# W033C.net
KiCad netlist of a schematic drawn in EAGLE
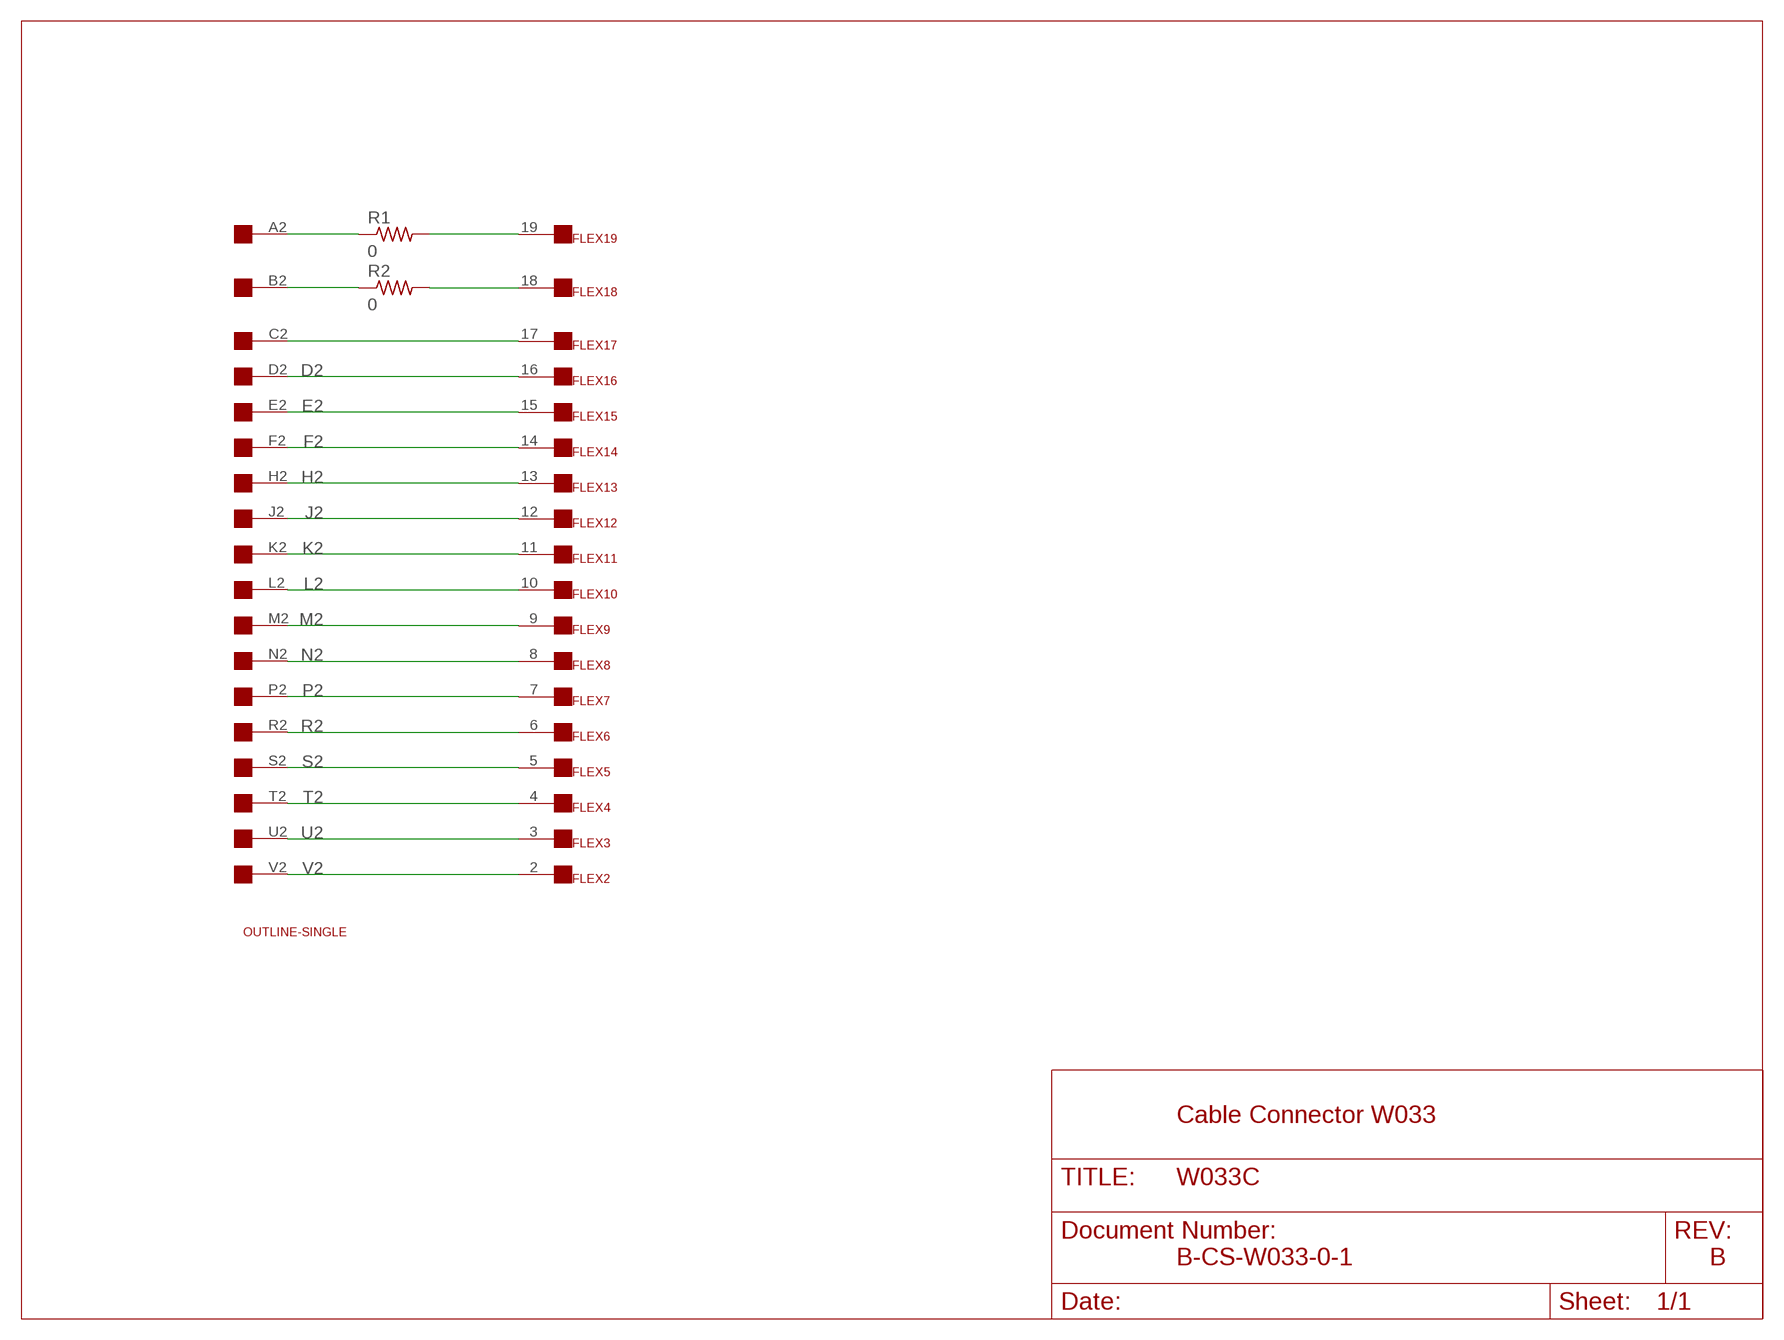
[diagram p0: schematic, sheet 1]

(export (version "E")
  (design (tool "Eeschema 10.0.6"))
  (components
    (comp (ref "FLEX")
      (value "FLEX19")
      (footprint "eagle-import:FLEX19")
      (libsource (lib "eagle-import") (part "FLEX19"))
    )
    (comp (ref "R1")
      (value "0")
      (footprint "eagle-import:0207_10")
      (libsource (lib "eagle-import") (part "R-US_0207/10"))
    )
    (comp (ref "R2")
      (value "0")
      (footprint "eagle-import:0207_10")
      (libsource (lib "eagle-import") (part "R-US_0207/10"))
    )
    (comp (ref "U$1")
      (value "OUTLINE-SINGLE")
      (footprint "eagle-import:SINGLE")
      (libsource (lib "eagle-import") (part "OUTLINE-SINGLE"))
    )
    (comp (ref "U$2")
      (value "EDGE-1")
      (footprint "eagle-import:EDGE-CON1")
      (libsource (lib "eagle-import") (part "EDGE-1"))
    )
  )
  (nets
    (net (code "1") (name "/D2") (class "Default")
      (node (ref "FLEX") (pin "16") (pinfunction "1_16") (pintype "passive"))
      (node (ref "U$2") (pin "D2") (pinfunction "1_D2") (pintype "bidirectional"))
    )
    (net (code "2") (name "/E2") (class "Default")
      (node (ref "FLEX") (pin "15") (pinfunction "1_15") (pintype "passive"))
      (node (ref "U$2") (pin "E2") (pinfunction "1_E2") (pintype "bidirectional"))
    )
    (net (code "3") (name "/F2") (class "Default")
      (node (ref "FLEX") (pin "14") (pinfunction "1_14") (pintype "passive"))
      (node (ref "U$2") (pin "F2") (pinfunction "1_F2") (pintype "bidirectional"))
    )
    (net (code "4") (name "/H2") (class "Default")
      (node (ref "FLEX") (pin "13") (pinfunction "1_13") (pintype "passive"))
      (node (ref "U$2") (pin "H2") (pinfunction "1_H2") (pintype "bidirectional"))
    )
    (net (code "5") (name "/J2") (class "Default")
      (node (ref "FLEX") (pin "12") (pinfunction "1_12") (pintype "passive"))
      (node (ref "U$2") (pin "J2") (pinfunction "1_J2") (pintype "bidirectional"))
    )
    (net (code "6") (name "/K2") (class "Default")
      (node (ref "FLEX") (pin "11") (pinfunction "1_11") (pintype "passive"))
      (node (ref "U$2") (pin "K2") (pinfunction "1_K2") (pintype "bidirectional"))
    )
    (net (code "7") (name "/L2") (class "Default")
      (node (ref "FLEX") (pin "10") (pinfunction "1_10") (pintype "passive"))
      (node (ref "U$2") (pin "L2") (pinfunction "1_L2") (pintype "bidirectional"))
    )
    (net (code "8") (name "/M2") (class "Default")
      (node (ref "FLEX") (pin "9") (pinfunction "1_9") (pintype "passive"))
      (node (ref "U$2") (pin "M2") (pinfunction "1_M2") (pintype "bidirectional"))
    )
    (net (code "9") (name "/N2") (class "Default")
      (node (ref "FLEX") (pin "8") (pinfunction "1_8") (pintype "passive"))
      (node (ref "U$2") (pin "N2") (pinfunction "1_N2") (pintype "bidirectional"))
    )
    (net (code "10") (name "/P2") (class "Default")
      (node (ref "FLEX") (pin "7") (pinfunction "1_7") (pintype "passive"))
      (node (ref "U$2") (pin "P2") (pinfunction "1_P2") (pintype "bidirectional"))
    )
    (net (code "11") (name "/R2") (class "Default")
      (node (ref "FLEX") (pin "6") (pinfunction "1_6") (pintype "passive"))
      (node (ref "U$2") (pin "R2") (pinfunction "1_R2") (pintype "bidirectional"))
    )
    (net (code "12") (name "/S2") (class "Default")
      (node (ref "FLEX") (pin "5") (pinfunction "1_5") (pintype "passive"))
      (node (ref "U$2") (pin "S2") (pinfunction "1_S2") (pintype "bidirectional"))
    )
    (net (code "13") (name "/T2") (class "Default")
      (node (ref "FLEX") (pin "4") (pinfunction "1_4") (pintype "passive"))
      (node (ref "U$2") (pin "T2") (pinfunction "1_T2") (pintype "bidirectional"))
    )
    (net (code "14") (name "/U2") (class "Default")
      (node (ref "FLEX") (pin "3") (pinfunction "1_3") (pintype "passive"))
      (node (ref "U$2") (pin "U2") (pinfunction "1_U2") (pintype "bidirectional"))
    )
    (net (code "15") (name "/V2") (class "Default")
      (node (ref "FLEX") (pin "2") (pinfunction "1_2") (pintype "passive"))
      (node (ref "U$2") (pin "V2") (pinfunction "1_V2") (pintype "bidirectional"))
    )
    (net (code "16") (name "Net-(FLEXI-1)") (class "Default")
      (node (ref "FLEX") (pin "17") (pinfunction "1_17") (pintype "passive"))
      (node (ref "U$2") (pin "C2") (pinfunction "1_C2") (pintype "bidirectional"))
    )
    (net (code "17") (name "Net-(FLEXJ-1)") (class "Default")
      (node (ref "FLEX") (pin "18") (pinfunction "1_18") (pintype "passive"))
      (node (ref "R2") (pin "2") (pinfunction "2_2") (pintype "passive"))
    )
    (net (code "18") (name "Net-(FLEXK-1)") (class "Default")
      (node (ref "FLEX") (pin "19") (pinfunction "1_19") (pintype "passive"))
      (node (ref "R1") (pin "2") (pinfunction "2_2") (pintype "passive"))
    )
    (net (code "19") (name "Net-(U$2A-1)") (class "Default")
      (node (ref "R1") (pin "1") (pinfunction "1_1") (pintype "passive"))
      (node (ref "U$2") (pin "A2") (pinfunction "1_A2") (pintype "bidirectional"))
    )
    (net (code "20") (name "Net-(U$2B-1)") (class "Default")
      (node (ref "R2") (pin "1") (pinfunction "1_1") (pintype "passive"))
      (node (ref "U$2") (pin "B2") (pinfunction "1_B2") (pintype "bidirectional"))
    )
  )
)
